# Dig_Encoder_Interface.net
KiCad netlist of a schematic drawn in Altium Designer
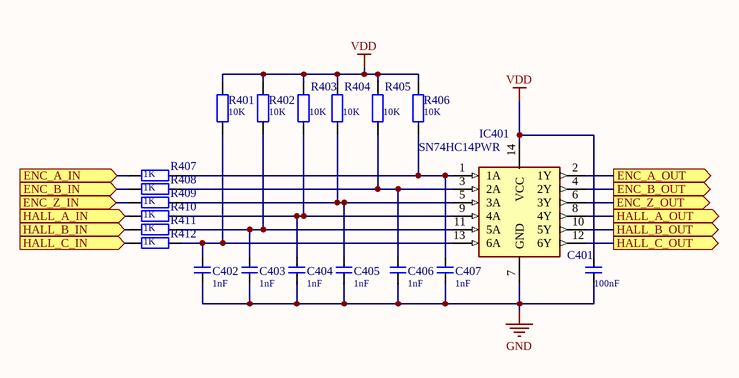
[diagram p0: Dig_Encoder_Interface.SchDoc]

(export (version "E")
  (design (tool "Eeschema 10.0.6"))
  (components
    (comp (ref "C401")
      (value "100nF")
      (footprint "CAPC1005X06N")
      (description "Capacitor")
      (fields (field (name "MPN") "GCM155R71H104KE02D") (field (name "Comment") "Cap"))
      (libsource (lib "SamacSys") (part "Cap"))
    )
    (comp (ref "C402")
      (value "1nF")
      (footprint "CAPC1005X06N")
      (description "Capacitor")
      (fields (field (name "MPN") "GRM155R71H102KA01D") (field (name "Comment") "Cap"))
      (libsource (lib "SamacSys") (part "Cap"))
    )
    (comp (ref "C403")
      (value "1nF")
      (footprint "CAPC1005X06N")
      (description "Capacitor")
      (fields (field (name "MPN") "GRM155R71H102KA01D") (field (name "Comment") "Cap"))
      (libsource (lib "SamacSys") (part "Cap"))
    )
    (comp (ref "C404")
      (value "1nF")
      (footprint "CAPC1005X06N")
      (description "Capacitor")
      (fields (field (name "MPN") "GRM155R71H102KA01D") (field (name "Comment") "Cap"))
      (libsource (lib "SamacSys") (part "Cap"))
    )
    (comp (ref "C405")
      (value "1nF")
      (footprint "CAPC1005X06N")
      (description "Capacitor")
      (fields (field (name "MPN") "GRM155R71H102KA01D") (field (name "Comment") "Cap"))
      (libsource (lib "SamacSys") (part "Cap"))
    )
    (comp (ref "C406")
      (value "1nF")
      (footprint "CAPC1005X06N")
      (description "Capacitor")
      (fields (field (name "MPN") "GRM155R71H102KA01D") (field (name "Comment") "Cap"))
      (libsource (lib "SamacSys") (part "Cap"))
    )
    (comp (ref "C407")
      (value "1nF")
      (footprint "CAPC1005X06N")
      (description "Capacitor")
      (fields (field (name "MPN") "GRM155R71H102KA01D") (field (name "Comment") "Cap"))
      (libsource (lib "SamacSys") (part "Cap"))
    )
    (comp (ref "IC401")
      (value "SN74HC14PWR")
      (footprint "SamacSys:SOP65P640X120-14N")
      (description "Integrated Circuit")
      (fields (field (name "MOUSER PART NUMBER") "595-SN74HC14PWR"))
      (libsource (lib "SamacSys") (part "SN74HC14PWR"))
    )
    (comp (ref "R401")
      (value "10K")
      (footprint "RESC1005X04N")
      (description "Resistor")
      (fields (field (name "MPN") "RC0402FR-0710KL") (field (name "Comment") "R"))
      (libsource (lib "SamacSys") (part "R"))
    )
    (comp (ref "R402")
      (value "10K")
      (footprint "RESC1005X04N")
      (description "Resistor")
      (fields (field (name "MPN") "RC0402FR-0710KL") (field (name "Comment") "R"))
      (libsource (lib "SamacSys") (part "R"))
    )
    (comp (ref "R403")
      (value "10K")
      (footprint "RESC1005X04N")
      (description "Resistor")
      (fields (field (name "MPN") "RC0402FR-0710KL") (field (name "Comment") "R"))
      (libsource (lib "SamacSys") (part "R"))
    )
    (comp (ref "R404")
      (value "10K")
      (footprint "RESC1005X04N")
      (description "Resistor")
      (fields (field (name "MPN") "RC0402FR-0710KL") (field (name "Comment") "R"))
      (libsource (lib "SamacSys") (part "R"))
    )
    (comp (ref "R405")
      (value "10K")
      (footprint "RESC1005X04N")
      (description "Resistor")
      (fields (field (name "MPN") "RC0402FR-0710KL") (field (name "Comment") "R"))
      (libsource (lib "SamacSys") (part "R"))
    )
    (comp (ref "R406")
      (value "10K")
      (footprint "RESC1005X04N")
      (description "Resistor")
      (fields (field (name "MPN") "RC0402FR-0710KL") (field (name "Comment") "R"))
      (libsource (lib "SamacSys") (part "R"))
    )
    (comp (ref "R407")
      (value "1K")
      (footprint "RESC1005X04N")
      (description "Resistor")
      (fields (field (name "MPN") "RC0402FR-071KL") (field (name "Comment") "R"))
      (libsource (lib "") (part "R_1"))
    )
    (comp (ref "R408")
      (value "1K")
      (footprint "RESC1005X04N")
      (description "Resistor")
      (fields (field (name "MPN") "RC0402FR-071KL") (field (name "Comment") "R"))
      (libsource (lib "") (part "R_1"))
    )
    (comp (ref "R409")
      (value "1K")
      (footprint "RESC1005X04N")
      (description "Resistor")
      (fields (field (name "MPN") "RC0402FR-071KL") (field (name "Comment") "R"))
      (libsource (lib "") (part "R_1"))
    )
    (comp (ref "R410")
      (value "1K")
      (footprint "RESC1005X04N")
      (description "Resistor")
      (fields (field (name "MPN") "RC0402FR-071KL") (field (name "Comment") "R"))
      (libsource (lib "") (part "R_1"))
    )
    (comp (ref "R411")
      (value "1K")
      (footprint "RESC1005X04N")
      (description "Resistor")
      (fields (field (name "MPN") "RC0402FR-071KL") (field (name "Comment") "R"))
      (libsource (lib "") (part "R_1"))
    )
    (comp (ref "R412")
      (value "1K")
      (footprint "RESC1005X04N")
      (description "Resistor")
      (fields (field (name "MPN") "RC0402FR-071KL") (field (name "Comment") "R"))
      (libsource (lib "") (part "R_1"))
    )
  )
  (nets
    (net (code "1") (name "/ENC_A_IN") (class "Default")
      (node (ref "R407") (pin "2") (pinfunction "2_2") (pintype "passive"))
    )
    (net (code "2") (name "/ENC_A_OUT") (class "Default")
      (node (ref "IC401") (pin "2") (pinfunction "1Y_2") (pintype "output"))
    )
    (net (code "3") (name "/ENC_B_IN") (class "Default")
      (node (ref "R408") (pin "2") (pinfunction "2_2") (pintype "passive"))
    )
    (net (code "4") (name "/ENC_B_OUT") (class "Default")
      (node (ref "IC401") (pin "4") (pinfunction "2Y_4") (pintype "output"))
    )
    (net (code "5") (name "/ENC_Z_IN") (class "Default")
      (node (ref "R409") (pin "2") (pinfunction "2_2") (pintype "passive"))
    )
    (net (code "6") (name "/ENC_Z_OUT") (class "Default")
      (node (ref "IC401") (pin "6") (pinfunction "3Y_6") (pintype "output"))
    )
    (net (code "7") (name "/HALL_A_IN") (class "Default")
      (node (ref "R410") (pin "2") (pinfunction "2_2") (pintype "passive"))
    )
    (net (code "8") (name "/HALL_A_OUT") (class "Default")
      (node (ref "IC401") (pin "8") (pinfunction "4Y_8") (pintype "output"))
    )
    (net (code "9") (name "/HALL_B_IN") (class "Default")
      (node (ref "R411") (pin "2") (pinfunction "2_2") (pintype "passive"))
    )
    (net (code "10") (name "/HALL_B_OUT") (class "Default")
      (node (ref "IC401") (pin "10") (pinfunction "5Y_10") (pintype "output"))
    )
    (net (code "11") (name "/HALL_C_IN") (class "Default")
      (node (ref "R412") (pin "2") (pinfunction "2_2") (pintype "passive"))
    )
    (net (code "12") (name "/HALL_C_OUT") (class "Default")
      (node (ref "IC401") (pin "12") (pinfunction "6Y_12") (pintype "output"))
    )
    (net (code "13") (name "GND") (class "Default")
      (node (ref "C401") (pin "1") (pinfunction "1_1") (pintype "passive"))
      (node (ref "C402") (pin "1") (pinfunction "1_1") (pintype "passive"))
      (node (ref "C403") (pin "1") (pinfunction "1_1") (pintype "passive"))
      (node (ref "C404") (pin "1") (pinfunction "1_1") (pintype "passive"))
      (node (ref "C405") (pin "1") (pinfunction "1_1") (pintype "passive"))
      (node (ref "C406") (pin "1") (pinfunction "1_1") (pintype "passive"))
      (node (ref "C407") (pin "1") (pinfunction "1_1") (pintype "passive"))
      (node (ref "IC401") (pin "7") (pinfunction "GND_7") (pintype "passive"))
    )
    (net (code "14") (name "Net-(IC401-1A)") (class "Default")
      (node (ref "C407") (pin "2") (pinfunction "2_2") (pintype "passive"))
      (node (ref "IC401") (pin "1") (pinfunction "1A_1") (pintype "input"))
      (node (ref "R406") (pin "1") (pinfunction "1_1") (pintype "passive"))
      (node (ref "R407") (pin "1") (pinfunction "1_1") (pintype "passive"))
    )
    (net (code "15") (name "Net-(IC401-2A)") (class "Default")
      (node (ref "C406") (pin "2") (pinfunction "2_2") (pintype "passive"))
      (node (ref "IC401") (pin "3") (pinfunction "2A_3") (pintype "input"))
      (node (ref "R405") (pin "1") (pinfunction "1_1") (pintype "passive"))
      (node (ref "R408") (pin "1") (pinfunction "1_1") (pintype "passive"))
    )
    (net (code "16") (name "Net-(IC401-3A)") (class "Default")
      (node (ref "C405") (pin "2") (pinfunction "2_2") (pintype "passive"))
      (node (ref "IC401") (pin "5") (pinfunction "3A_5") (pintype "input"))
      (node (ref "R404") (pin "1") (pinfunction "1_1") (pintype "passive"))
      (node (ref "R409") (pin "1") (pinfunction "1_1") (pintype "passive"))
    )
    (net (code "17") (name "Net-(IC401-4A)") (class "Default")
      (node (ref "C404") (pin "2") (pinfunction "2_2") (pintype "passive"))
      (node (ref "IC401") (pin "9") (pinfunction "4A_9") (pintype "input"))
      (node (ref "R403") (pin "1") (pinfunction "1_1") (pintype "passive"))
      (node (ref "R410") (pin "1") (pinfunction "1_1") (pintype "passive"))
    )
    (net (code "18") (name "Net-(IC401-5A)") (class "Default")
      (node (ref "C403") (pin "2") (pinfunction "2_2") (pintype "passive"))
      (node (ref "IC401") (pin "11") (pinfunction "5A_11") (pintype "input"))
      (node (ref "R402") (pin "1") (pinfunction "1_1") (pintype "passive"))
      (node (ref "R411") (pin "1") (pinfunction "1_1") (pintype "passive"))
    )
    (net (code "19") (name "Net-(IC401-6A)") (class "Default")
      (node (ref "C402") (pin "2") (pinfunction "2_2") (pintype "passive"))
      (node (ref "IC401") (pin "13") (pinfunction "6A_13") (pintype "input"))
      (node (ref "R401") (pin "1") (pinfunction "1_1") (pintype "passive"))
      (node (ref "R412") (pin "1") (pinfunction "1_1") (pintype "passive"))
    )
    (net (code "20") (name "VDD") (class "Default")
      (node (ref "C401") (pin "2") (pinfunction "2_2") (pintype "passive"))
      (node (ref "IC401") (pin "14") (pinfunction "VCC_14") (pintype "passive"))
      (node (ref "R401") (pin "2") (pinfunction "2_2") (pintype "passive"))
      (node (ref "R402") (pin "2") (pinfunction "2_2") (pintype "passive"))
      (node (ref "R403") (pin "2") (pinfunction "2_2") (pintype "passive"))
      (node (ref "R404") (pin "2") (pinfunction "2_2") (pintype "passive"))
      (node (ref "R405") (pin "2") (pinfunction "2_2") (pintype "passive"))
      (node (ref "R406") (pin "2") (pinfunction "2_2") (pintype "passive"))
    )
  )
)
